# WhatFrankShould_veDone.net
KiCad netlist of a schematic drawn in EAGLE
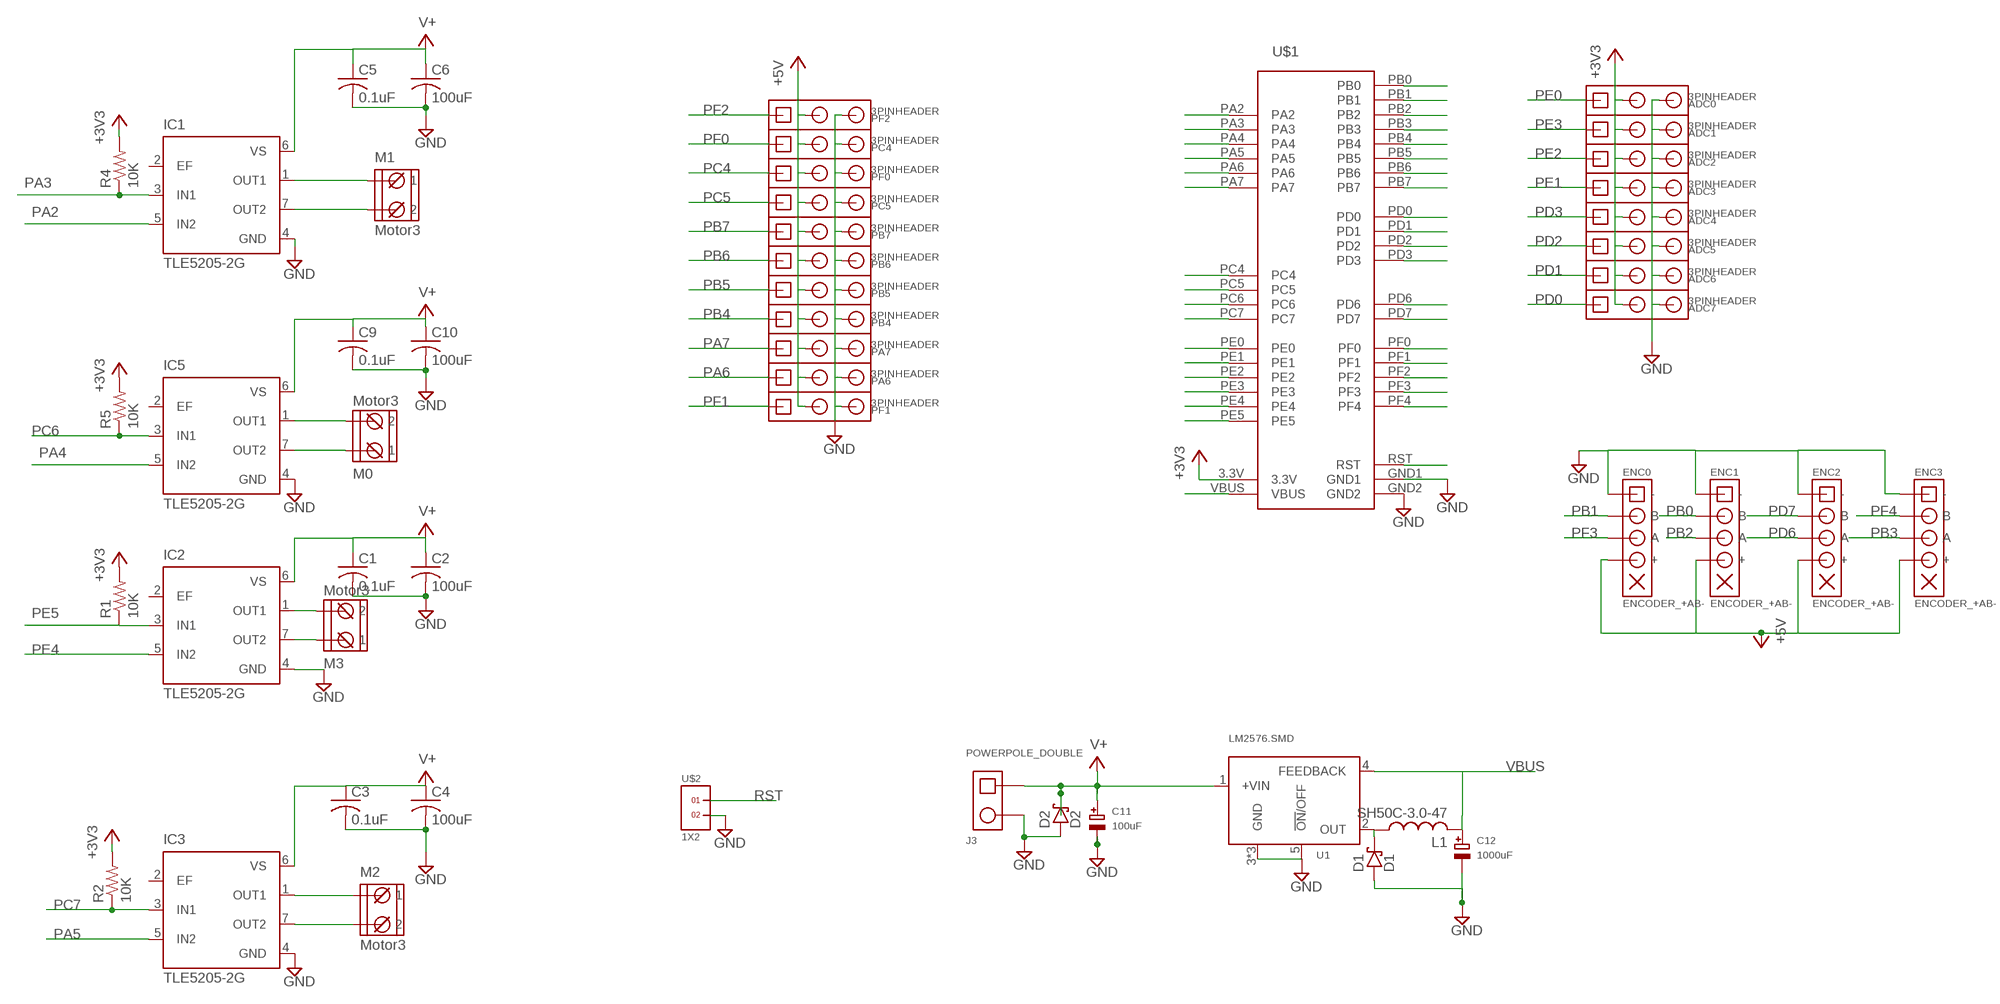
[diagram p0: schematic, sheet 1]

(export (version "E")
  (design (tool "Eeschema 10.0.6"))
  (components
    (comp (ref "ADC0")
      (value "3PINHEADER")
      (footprint "eagle-import:3PINHEADER")
      (libsource (lib "eagle-import") (part "3PINHEADER"))
    )
    (comp (ref "ADC1")
      (value "3PINHEADER")
      (footprint "eagle-import:3PINHEADER")
      (libsource (lib "eagle-import") (part "3PINHEADER"))
    )
    (comp (ref "ADC2")
      (value "3PINHEADER")
      (footprint "eagle-import:3PINHEADER")
      (libsource (lib "eagle-import") (part "3PINHEADER"))
    )
    (comp (ref "ADC3")
      (value "3PINHEADER")
      (footprint "eagle-import:3PINHEADER")
      (libsource (lib "eagle-import") (part "3PINHEADER"))
    )
    (comp (ref "ADC4")
      (value "3PINHEADER")
      (footprint "eagle-import:3PINHEADER")
      (libsource (lib "eagle-import") (part "3PINHEADER"))
    )
    (comp (ref "ADC5")
      (value "3PINHEADER")
      (footprint "eagle-import:3PINHEADER")
      (libsource (lib "eagle-import") (part "3PINHEADER"))
    )
    (comp (ref "ADC6")
      (value "3PINHEADER")
      (footprint "eagle-import:3PINHEADER")
      (libsource (lib "eagle-import") (part "3PINHEADER"))
    )
    (comp (ref "ADC7")
      (value "3PINHEADER")
      (footprint "eagle-import:3PINHEADER")
      (libsource (lib "eagle-import") (part "3PINHEADER"))
    )
    (comp (ref "C1")
      (value "0.1uF")
      (footprint "eagle-import:C0603")
      (libsource (lib "eagle-import") (part "C-USC0603"))
    )
    (comp (ref "C2")
      (value "100uF")
      (footprint "eagle-import:C0603")
      (libsource (lib "eagle-import") (part "C-USC0603"))
    )
    (comp (ref "C3")
      (value "0.1uF")
      (footprint "eagle-import:C0603")
      (libsource (lib "eagle-import") (part "C-USC0603"))
    )
    (comp (ref "C4")
      (value "100uF")
      (footprint "eagle-import:C0603")
      (libsource (lib "eagle-import") (part "C-USC0603"))
    )
    (comp (ref "C5")
      (value "0.1uF")
      (footprint "eagle-import:C0603")
      (libsource (lib "eagle-import") (part "C-USC0603"))
    )
    (comp (ref "C6")
      (value "100uF")
      (footprint "eagle-import:C0603")
      (libsource (lib "eagle-import") (part "C-USC0603"))
    )
    (comp (ref "C9")
      (value "0.1uF")
      (footprint "eagle-import:C0603")
      (libsource (lib "eagle-import") (part "C-USC0603"))
    )
    (comp (ref "C10")
      (value "100uF")
      (footprint "eagle-import:C0603")
      (libsource (lib "eagle-import") (part "C-USC0603"))
    )
    (comp (ref "C11")
      (value "100uF")
      (footprint "eagle-import:PANASONIC_D")
      (libsource (lib "eagle-import") (part "CAP_ELECTROLYTICPANASONIC_D"))
    )
    (comp (ref "C12")
      (value "1000uF")
      (footprint "eagle-import:PANASONIC_D")
      (libsource (lib "eagle-import") (part "CAP_ELECTROLYTICPANASONIC_D"))
    )
    (comp (ref "D1")
      (value "D1")
      (footprint "eagle-import:DIODE_17MM")
      (libsource (lib "eagle-import") (part "1N5820-D"))
    )
    (comp (ref "D2")
      (value "D2")
      (footprint "eagle-import:DIODE_17MM")
      (libsource (lib "eagle-import") (part "1N5820-D"))
    )
    (comp (ref "ENC0")
      (value "ENCODER_+AB-")
      (footprint "eagle-import:0.1IN_HEADER_1X5")
      (libsource (lib "eagle-import") (part "ENCODER_+AB-"))
    )
    (comp (ref "ENC1")
      (value "ENCODER_+AB-")
      (footprint "eagle-import:0.1IN_HEADER_1X5")
      (libsource (lib "eagle-import") (part "ENCODER_+AB-"))
    )
    (comp (ref "ENC2")
      (value "ENCODER_+AB-")
      (footprint "eagle-import:0.1IN_HEADER_1X5")
      (libsource (lib "eagle-import") (part "ENCODER_+AB-"))
    )
    (comp (ref "ENC3")
      (value "ENCODER_+AB-")
      (footprint "eagle-import:0.1IN_HEADER_1X5")
      (libsource (lib "eagle-import") (part "ENCODER_+AB-"))
    )
    (comp (ref "IC1")
      (value "TLE5205-2G")
      (footprint "eagle-import:P-TO263-7-1")
      (libsource (lib "eagle-import") (part "TLE5205-2G"))
    )
    (comp (ref "IC2")
      (value "TLE5205-2G")
      (footprint "eagle-import:P-TO263-7-1")
      (libsource (lib "eagle-import") (part "TLE5205-2G"))
    )
    (comp (ref "IC3")
      (value "TLE5205-2G")
      (footprint "eagle-import:P-TO263-7-1")
      (libsource (lib "eagle-import") (part "TLE5205-2G"))
    )
    (comp (ref "IC5")
      (value "TLE5205-2G")
      (footprint "eagle-import:P-TO263-7-1")
      (libsource (lib "eagle-import") (part "TLE5205-2G"))
    )
    (comp (ref "J3")
      (value "POWERPOLE_DOUBLE")
      (footprint "eagle-import:POWERPOLE_DOUBLE")
      (libsource (lib "eagle-import") (part "POWERPOLE_DOUBLE"))
    )
    (comp (ref "L1")
      (value "SH50C-3.0-47")
      (footprint "eagle-import:SH50-C2")
      (libsource (lib "eagle-import") (part "SH50C-3.0-47"))
    )
    (comp (ref "M0")
      (value "Motor3")
      (footprint "eagle-import:PHOENIXSCREWTERMINAL_2")
      (libsource (lib "eagle-import") (part "PHOENIXSCREWTERMINAL_2"))
    )
    (comp (ref "M1")
      (value "Motor3")
      (footprint "eagle-import:PHOENIXSCREWTERMINAL_2")
      (libsource (lib "eagle-import") (part "PHOENIXSCREWTERMINAL_2"))
    )
    (comp (ref "M2")
      (value "Motor3")
      (footprint "eagle-import:PHOENIXSCREWTERMINAL_2")
      (libsource (lib "eagle-import") (part "PHOENIXSCREWTERMINAL_2"))
    )
    (comp (ref "M3")
      (value "Motor3")
      (footprint "eagle-import:PHOENIXSCREWTERMINAL_2")
      (libsource (lib "eagle-import") (part "PHOENIXSCREWTERMINAL_2"))
    )
    (comp (ref "PA6")
      (value "3PINHEADER")
      (footprint "eagle-import:3PINHEADER")
      (libsource (lib "eagle-import") (part "3PINHEADER"))
    )
    (comp (ref "PA7")
      (value "3PINHEADER")
      (footprint "eagle-import:3PINHEADER")
      (libsource (lib "eagle-import") (part "3PINHEADER"))
    )
    (comp (ref "PB4")
      (value "3PINHEADER")
      (footprint "eagle-import:3PINHEADER")
      (libsource (lib "eagle-import") (part "3PINHEADER"))
    )
    (comp (ref "PB5")
      (value "3PINHEADER")
      (footprint "eagle-import:3PINHEADER")
      (libsource (lib "eagle-import") (part "3PINHEADER"))
    )
    (comp (ref "PB6")
      (value "3PINHEADER")
      (footprint "eagle-import:3PINHEADER")
      (libsource (lib "eagle-import") (part "3PINHEADER"))
    )
    (comp (ref "PB7")
      (value "3PINHEADER")
      (footprint "eagle-import:3PINHEADER")
      (libsource (lib "eagle-import") (part "3PINHEADER"))
    )
    (comp (ref "PC4")
      (value "3PINHEADER")
      (footprint "eagle-import:3PINHEADER")
      (libsource (lib "eagle-import") (part "3PINHEADER"))
    )
    (comp (ref "PC5")
      (value "3PINHEADER")
      (footprint "eagle-import:3PINHEADER")
      (libsource (lib "eagle-import") (part "3PINHEADER"))
    )
    (comp (ref "PF0")
      (value "3PINHEADER")
      (footprint "eagle-import:3PINHEADER")
      (libsource (lib "eagle-import") (part "3PINHEADER"))
    )
    (comp (ref "PF1")
      (value "3PINHEADER")
      (footprint "eagle-import:3PINHEADER")
      (libsource (lib "eagle-import") (part "3PINHEADER"))
    )
    (comp (ref "PF2")
      (value "3PINHEADER")
      (footprint "eagle-import:3PINHEADER")
      (libsource (lib "eagle-import") (part "3PINHEADER"))
    )
    (comp (ref "R1")
      (value "10K")
      (footprint "eagle-import:R0603")
      (libsource (lib "eagle-import") (part "R-US_R0603"))
    )
    (comp (ref "R2")
      (value "10K")
      (footprint "eagle-import:R0603")
      (libsource (lib "eagle-import") (part "R-US_R0603"))
    )
    (comp (ref "R4")
      (value "10K")
      (footprint "eagle-import:R0603")
      (libsource (lib "eagle-import") (part "R-US_R0603"))
    )
    (comp (ref "R5")
      (value "10K")
      (footprint "eagle-import:R0603")
      (libsource (lib "eagle-import") (part "R-US_R0603"))
    )
    (comp (ref "U$1")
      (value "STELLARIS-LAUNCHPADSTELLARIS-LAUNCHPAD-XL")
      (footprint "eagle-import:LAUNCHPAD-XL")
      (libsource (lib "eagle-import") (part "STELLARIS-LAUNCHPADSTELLARIS-LAUNCHPAD-XL"))
    )
    (comp (ref "U$2")
      (value "1X2")
      (footprint "eagle-import:1X2")
      (libsource (lib "eagle-import") (part "1X2"))
    )
    (comp (ref "U1")
      (value "LM2576.SMD")
      (footprint "eagle-import:KTT0005B")
      (libsource (lib "eagle-import") (part "LM2576.SMD"))
    )
  )
  (nets
    (net (code "1") (name "+3V3") (class "Default")
      (node (ref "ADC0") (pin "2") (pinfunction "2_2") (pintype "bidirectional"))
      (node (ref "ADC1") (pin "2") (pinfunction "2_2") (pintype "bidirectional"))
      (node (ref "ADC2") (pin "2") (pinfunction "2_2") (pintype "bidirectional"))
      (node (ref "ADC3") (pin "2") (pinfunction "2_2") (pintype "bidirectional"))
      (node (ref "ADC4") (pin "2") (pinfunction "2_2") (pintype "bidirectional"))
      (node (ref "ADC5") (pin "2") (pinfunction "2_2") (pintype "bidirectional"))
      (node (ref "ADC6") (pin "2") (pinfunction "2_2") (pintype "bidirectional"))
      (node (ref "ADC7") (pin "2") (pinfunction "2_2") (pintype "bidirectional"))
      (node (ref "R1") (pin "2") (pinfunction "2_2") (pintype "passive"))
      (node (ref "R2") (pin "2") (pinfunction "2_2") (pintype "passive"))
      (node (ref "R4") (pin "2") (pinfunction "2_2") (pintype "passive"))
      (node (ref "R5") (pin "2") (pinfunction "2_2") (pintype "passive"))
      (node (ref "U$1") (pin "3.3V") (pinfunction "3.3V_3.3V") (pintype "power_in"))
    )
    (net (code "2") (name "+5V") (class "Default")
      (node (ref "ENC0") (pin "4") (pinfunction "+_4") (pintype "bidirectional"))
      (node (ref "ENC1") (pin "4") (pinfunction "+_4") (pintype "bidirectional"))
      (node (ref "ENC2") (pin "4") (pinfunction "+_4") (pintype "bidirectional"))
      (node (ref "ENC3") (pin "4") (pinfunction "+_4") (pintype "bidirectional"))
      (node (ref "PA6") (pin "2") (pinfunction "2_2") (pintype "bidirectional"))
      (node (ref "PA7") (pin "2") (pinfunction "2_2") (pintype "bidirectional"))
      (node (ref "PB4") (pin "2") (pinfunction "2_2") (pintype "bidirectional"))
      (node (ref "PB5") (pin "2") (pinfunction "2_2") (pintype "bidirectional"))
      (node (ref "PB6") (pin "2") (pinfunction "2_2") (pintype "bidirectional"))
      (node (ref "PB7") (pin "2") (pinfunction "2_2") (pintype "bidirectional"))
      (node (ref "PC4") (pin "2") (pinfunction "2_2") (pintype "bidirectional"))
      (node (ref "PC5") (pin "2") (pinfunction "2_2") (pintype "bidirectional"))
      (node (ref "PF0") (pin "2") (pinfunction "2_2") (pintype "bidirectional"))
      (node (ref "PF1") (pin "2") (pinfunction "2_2") (pintype "bidirectional"))
      (node (ref "PF2") (pin "2") (pinfunction "2_2") (pintype "bidirectional"))
    )
    (net (code "3") (name "/PA2") (class "Default")
      (node (ref "IC1") (pin "5") (pinfunction "IN2_5") (pintype "input"))
      (node (ref "U$1") (pin "PA2") (pinfunction "PA2_PA2") (pintype "bidirectional"))
    )
    (net (code "4") (name "/PA3") (class "Default")
      (node (ref "IC1") (pin "3") (pinfunction "IN1_3") (pintype "input"))
      (node (ref "R4") (pin "1") (pinfunction "1_1") (pintype "passive"))
      (node (ref "U$1") (pin "PA3") (pinfunction "PA3_PA3") (pintype "bidirectional"))
    )
    (net (code "5") (name "/PA4") (class "Default")
      (node (ref "IC5") (pin "5") (pinfunction "IN2_5") (pintype "input"))
      (node (ref "U$1") (pin "PA4") (pinfunction "PA4_PA4") (pintype "bidirectional"))
    )
    (net (code "6") (name "/PA5") (class "Default")
      (node (ref "IC3") (pin "5") (pinfunction "IN2_5") (pintype "input"))
      (node (ref "U$1") (pin "PA5") (pinfunction "PA5_PA5") (pintype "bidirectional"))
    )
    (net (code "7") (name "/PA6") (class "Default")
      (node (ref "PA6") (pin "1") (pinfunction "1_1") (pintype "bidirectional"))
      (node (ref "U$1") (pin "PA6") (pinfunction "PA6_PA6") (pintype "bidirectional"))
    )
    (net (code "8") (name "/PA7") (class "Default")
      (node (ref "PA7") (pin "1") (pinfunction "1_1") (pintype "bidirectional"))
      (node (ref "U$1") (pin "PA7") (pinfunction "PA7_PA7") (pintype "bidirectional"))
    )
    (net (code "9") (name "/PB0") (class "Default")
      (node (ref "ENC1") (pin "2") (pinfunction "B_2") (pintype "bidirectional"))
      (node (ref "U$1") (pin "PB0") (pinfunction "PB0_PB0") (pintype "bidirectional"))
    )
    (net (code "10") (name "/PB1") (class "Default")
      (node (ref "ENC0") (pin "2") (pinfunction "B_2") (pintype "bidirectional"))
      (node (ref "U$1") (pin "PB1") (pinfunction "PB1_PB1") (pintype "bidirectional"))
    )
    (net (code "11") (name "/PB2") (class "Default")
      (node (ref "ENC1") (pin "3") (pinfunction "A_3") (pintype "bidirectional"))
      (node (ref "U$1") (pin "PB2") (pinfunction "PB2_PB2") (pintype "bidirectional"))
    )
    (net (code "12") (name "/PB3") (class "Default")
      (node (ref "ENC3") (pin "3") (pinfunction "A_3") (pintype "bidirectional"))
      (node (ref "U$1") (pin "PB3") (pinfunction "PB3_PB3") (pintype "bidirectional"))
    )
    (net (code "13") (name "/PB4") (class "Default")
      (node (ref "PB4") (pin "1") (pinfunction "1_1") (pintype "bidirectional"))
      (node (ref "U$1") (pin "PB4") (pinfunction "PB4_PB4") (pintype "bidirectional"))
    )
    (net (code "14") (name "/PB5") (class "Default")
      (node (ref "PB5") (pin "1") (pinfunction "1_1") (pintype "bidirectional"))
      (node (ref "U$1") (pin "PB5") (pinfunction "PB5_PB5") (pintype "bidirectional"))
    )
    (net (code "15") (name "/PB6") (class "Default")
      (node (ref "PB6") (pin "1") (pinfunction "1_1") (pintype "bidirectional"))
      (node (ref "U$1") (pin "PB6") (pinfunction "PB6_PB6") (pintype "bidirectional"))
    )
    (net (code "16") (name "/PB7") (class "Default")
      (node (ref "PB7") (pin "1") (pinfunction "1_1") (pintype "bidirectional"))
      (node (ref "U$1") (pin "PB7") (pinfunction "PB7_PB7") (pintype "bidirectional"))
    )
    (net (code "17") (name "/PC4") (class "Default")
      (node (ref "PF0") (pin "1") (pinfunction "1_1") (pintype "bidirectional"))
      (node (ref "U$1") (pin "PC4") (pinfunction "PC4_PC4") (pintype "bidirectional"))
    )
    (net (code "18") (name "/PC5") (class "Default")
      (node (ref "PC5") (pin "1") (pinfunction "1_1") (pintype "bidirectional"))
      (node (ref "U$1") (pin "PC5") (pinfunction "PC5_PC5") (pintype "bidirectional"))
    )
    (net (code "19") (name "/PC6") (class "Default")
      (node (ref "IC5") (pin "3") (pinfunction "IN1_3") (pintype "input"))
      (node (ref "R5") (pin "1") (pinfunction "1_1") (pintype "passive"))
      (node (ref "U$1") (pin "PC6") (pinfunction "PC6_PC6") (pintype "bidirectional"))
    )
    (net (code "20") (name "/PC7") (class "Default")
      (node (ref "IC3") (pin "3") (pinfunction "IN1_3") (pintype "input"))
      (node (ref "R2") (pin "1") (pinfunction "1_1") (pintype "passive"))
      (node (ref "U$1") (pin "PC7") (pinfunction "PC7_PC7") (pintype "bidirectional"))
    )
    (net (code "21") (name "/PD0") (class "Default")
      (node (ref "ADC7") (pin "1") (pinfunction "1_1") (pintype "bidirectional"))
      (node (ref "U$1") (pin "PD0") (pinfunction "PD0_PD0") (pintype "bidirectional"))
    )
    (net (code "22") (name "/PD1") (class "Default")
      (node (ref "ADC6") (pin "1") (pinfunction "1_1") (pintype "bidirectional"))
      (node (ref "U$1") (pin "PD1") (pinfunction "PD1_PD1") (pintype "bidirectional"))
    )
    (net (code "23") (name "/PD2") (class "Default")
      (node (ref "ADC5") (pin "1") (pinfunction "1_1") (pintype "bidirectional"))
      (node (ref "U$1") (pin "PD2") (pinfunction "PD2_PD2") (pintype "bidirectional"))
    )
    (net (code "24") (name "/PD3") (class "Default")
      (node (ref "ADC4") (pin "1") (pinfunction "1_1") (pintype "bidirectional"))
      (node (ref "U$1") (pin "PD3") (pinfunction "PD3_PD3") (pintype "bidirectional"))
    )
    (net (code "25") (name "/PD6") (class "Default")
      (node (ref "ENC2") (pin "3") (pinfunction "A_3") (pintype "bidirectional"))
      (node (ref "U$1") (pin "PD6") (pinfunction "PD6_PD6") (pintype "bidirectional"))
    )
    (net (code "26") (name "/PD7") (class "Default")
      (node (ref "ENC2") (pin "2") (pinfunction "B_2") (pintype "bidirectional"))
      (node (ref "U$1") (pin "PD7") (pinfunction "PD7_PD7") (pintype "bidirectional"))
    )
    (net (code "27") (name "/PE0") (class "Default")
      (node (ref "ADC0") (pin "1") (pinfunction "1_1") (pintype "bidirectional"))
      (node (ref "U$1") (pin "PE0") (pinfunction "PE0_PE0") (pintype "bidirectional"))
    )
    (net (code "28") (name "/PE1") (class "Default")
      (node (ref "ADC3") (pin "1") (pinfunction "1_1") (pintype "bidirectional"))
      (node (ref "U$1") (pin "PE1") (pinfunction "PE1_PE1") (pintype "bidirectional"))
    )
    (net (code "29") (name "/PE2") (class "Default")
      (node (ref "ADC2") (pin "1") (pinfunction "1_1") (pintype "bidirectional"))
      (node (ref "U$1") (pin "PE2") (pinfunction "PE2_PE2") (pintype "bidirectional"))
    )
    (net (code "30") (name "/PE3") (class "Default")
      (node (ref "ADC1") (pin "1") (pinfunction "1_1") (pintype "bidirectional"))
      (node (ref "U$1") (pin "PE3") (pinfunction "PE3_PE3") (pintype "bidirectional"))
    )
    (net (code "31") (name "/PE4") (class "Default")
      (node (ref "IC2") (pin "5") (pinfunction "IN2_5") (pintype "input"))
      (node (ref "U$1") (pin "PE4") (pinfunction "PE4_PE4") (pintype "bidirectional"))
    )
    (net (code "32") (name "/PE5") (class "Default")
      (node (ref "IC2") (pin "3") (pinfunction "IN1_3") (pintype "input"))
      (node (ref "R1") (pin "1") (pinfunction "1_1") (pintype "passive"))
      (node (ref "U$1") (pin "PE5") (pinfunction "PE5_PE5") (pintype "bidirectional"))
    )
    (net (code "33") (name "/PF0") (class "Default")
      (node (ref "PC4") (pin "1") (pinfunction "1_1") (pintype "bidirectional"))
      (node (ref "U$1") (pin "PF0") (pinfunction "PF0_PF0") (pintype "bidirectional"))
    )
    (net (code "34") (name "/PF1") (class "Default")
      (node (ref "PF1") (pin "1") (pinfunction "1_1") (pintype "bidirectional"))
      (node (ref "U$1") (pin "PF1") (pinfunction "PF1_PF1") (pintype "bidirectional"))
    )
    (net (code "35") (name "/PF2") (class "Default")
      (node (ref "PF2") (pin "1") (pinfunction "1_1") (pintype "bidirectional"))
      (node (ref "U$1") (pin "PF2") (pinfunction "PF2_PF2") (pintype "bidirectional"))
    )
    (net (code "36") (name "/PF3") (class "Default")
      (node (ref "ENC0") (pin "3") (pinfunction "A_3") (pintype "bidirectional"))
      (node (ref "U$1") (pin "PF3") (pinfunction "PF3_PF3") (pintype "bidirectional"))
    )
    (net (code "37") (name "/PF4") (class "Default")
      (node (ref "ENC3") (pin "2") (pinfunction "B_2") (pintype "bidirectional"))
      (node (ref "U$1") (pin "PF4") (pinfunction "PF4_PF4") (pintype "bidirectional"))
    )
    (net (code "38") (name "/RST") (class "Default")
      (node (ref "U$1") (pin "RST") (pinfunction "RST_RST") (pintype "power_in"))
      (node (ref "U$2") (pin "1") (pinfunction "1_1") (pintype "bidirectional"))
    )
    (net (code "39") (name "/VBUS") (class "Default")
      (node (ref "C12") (pin "+") (pinfunction "+_+") (pintype "passive"))
      (node (ref "L1") (pin "P$2") (pinfunction "2_P$2") (pintype "passive"))
      (node (ref "U$1") (pin "VBUS") (pinfunction "VBUS_VBUS") (pintype "power_in"))
      (node (ref "U1") (pin "4") (pinfunction "FEEDBACK_4") (pintype "bidirectional"))
    )
    (net (code "40") (name "GND") (class "Default")
      (node (ref "ADC0") (pin "3") (pinfunction "3_3") (pintype "bidirectional"))
      (node (ref "ADC1") (pin "3") (pinfunction "3_3") (pintype "bidirectional"))
      (node (ref "ADC2") (pin "3") (pinfunction "3_3") (pintype "bidirectional"))
      (node (ref "ADC3") (pin "3") (pinfunction "3_3") (pintype "bidirectional"))
      (node (ref "ADC4") (pin "3") (pinfunction "3_3") (pintype "bidirectional"))
      (node (ref "ADC5") (pin "3") (pinfunction "3_3") (pintype "bidirectional"))
      (node (ref "ADC6") (pin "3") (pinfunction "3_3") (pintype "bidirectional"))
      (node (ref "ADC7") (pin "3") (pinfunction "3_3") (pintype "bidirectional"))
      (node (ref "C1") (pin "2") (pinfunction "2_2") (pintype "passive"))
      (node (ref "C10") (pin "2") (pinfunction "2_2") (pintype "passive"))
      (node (ref "C11") (pin "-") (pinfunction "-_-") (pintype "passive"))
      (node (ref "C12") (pin "-") (pinfunction "-_-") (pintype "passive"))
      (node (ref "C2") (pin "2") (pinfunction "2_2") (pintype "passive"))
      (node (ref "C3") (pin "2") (pinfunction "2_2") (pintype "passive"))
      (node (ref "C4") (pin "2") (pinfunction "2_2") (pintype "passive"))
      (node (ref "C5") (pin "2") (pinfunction "2_2") (pintype "passive"))
      (node (ref "C6") (pin "2") (pinfunction "2_2") (pintype "passive"))
      (node (ref "C9") (pin "2") (pinfunction "2_2") (pintype "passive"))
      (node (ref "D1") (pin "2") (pinfunction "A_2") (pintype "passive"))
      (node (ref "D2") (pin "2") (pinfunction "A_2") (pintype "passive"))
      (node (ref "ENC0") (pin "1") (pinfunction "-_1") (pintype "bidirectional"))
      (node (ref "ENC1") (pin "1") (pinfunction "-_1") (pintype "bidirectional"))
      (node (ref "ENC2") (pin "1") (pinfunction "-_1") (pintype "bidirectional"))
      (node (ref "ENC3") (pin "1") (pinfunction "-_1") (pintype "bidirectional"))
      (node (ref "IC1") (pin "4") (pinfunction "GND_4") (pintype "power_in"))
      (node (ref "IC2") (pin "4") (pinfunction "GND_4") (pintype "power_in"))
      (node (ref "IC3") (pin "4") (pinfunction "GND_4") (pintype "power_in"))
      (node (ref "IC5") (pin "4") (pinfunction "GND_4") (pintype "power_in"))
      (node (ref "J3") (pin "2") (pinfunction "2_2") (pintype "bidirectional"))
      (node (ref "PA6") (pin "3") (pinfunction "3_3") (pintype "bidirectional"))
      (node (ref "PA7") (pin "3") (pinfunction "3_3") (pintype "bidirectional"))
      (node (ref "PB4") (pin "3") (pinfunction "3_3") (pintype "bidirectional"))
      (node (ref "PB5") (pin "3") (pinfunction "3_3") (pintype "bidirectional"))
      (node (ref "PB6") (pin "3") (pinfunction "3_3") (pintype "bidirectional"))
      (node (ref "PB7") (pin "3") (pinfunction "3_3") (pintype "bidirectional"))
      (node (ref "PC4") (pin "3") (pinfunction "3_3") (pintype "bidirectional"))
      (node (ref "PC5") (pin "3") (pinfunction "3_3") (pintype "bidirectional"))
      (node (ref "PF0") (pin "3") (pinfunction "3_3") (pintype "bidirectional"))
      (node (ref "PF1") (pin "3") (pinfunction "3_3") (pintype "bidirectional"))
      (node (ref "PF2") (pin "3") (pinfunction "3_3") (pintype "bidirectional"))
      (node (ref "U$1") (pin "GND1") (pinfunction "GND1_GND1") (pintype "bidirectional"))
      (node (ref "U$1") (pin "GND2") (pinfunction "GND2_GND2") (pintype "power_in"))
      (node (ref "U$2") (pin "2") (pinfunction "2_2") (pintype "bidirectional"))
      (node (ref "U1") (pin "3") (pinfunction "GND_3") (pintype "bidirectional"))
      (node (ref "U1") (pin "5") (pinfunction "~{ON}/OFF_5") (pintype "bidirectional"))
      (node (ref "U1") (pin "GROUND") (pinfunction "GND_GROUND") (pintype "bidirectional"))
      (node (ref "U1") (pin "GROUND@1") (pinfunction "GND_GROUND@1") (pintype "bidirectional"))
    )
    (net (code "41") (name "Net-(D1-C)") (class "Default")
      (node (ref "D1") (pin "1") (pinfunction "C_1") (pintype "passive"))
      (node (ref "L1") (pin "P$1") (pinfunction "1_P$1") (pintype "passive"))
      (node (ref "U1") (pin "2") (pinfunction "OUT_2") (pintype "bidirectional"))
    )
    (net (code "42") (name "Net-(IC1-OUT1)") (class "Default")
      (node (ref "IC1") (pin "1") (pinfunction "OUT1_1") (pintype "output"))
      (node (ref "M1") (pin "1") (pinfunction "1_1") (pintype "bidirectional"))
    )
    (net (code "43") (name "Net-(IC1-OUT2)") (class "Default")
      (node (ref "IC1") (pin "7") (pinfunction "OUT2_7") (pintype "output"))
      (node (ref "M1") (pin "2") (pinfunction "2_2") (pintype "bidirectional"))
    )
    (net (code "44") (name "Net-(IC2-OUT1)") (class "Default")
      (node (ref "IC2") (pin "1") (pinfunction "OUT1_1") (pintype "output"))
      (node (ref "M3") (pin "2") (pinfunction "2_2") (pintype "bidirectional"))
    )
    (net (code "45") (name "Net-(IC2-OUT2)") (class "Default")
      (node (ref "IC2") (pin "7") (pinfunction "OUT2_7") (pintype "output"))
      (node (ref "M3") (pin "1") (pinfunction "1_1") (pintype "bidirectional"))
    )
    (net (code "46") (name "Net-(IC3-OUT1)") (class "Default")
      (node (ref "IC3") (pin "1") (pinfunction "OUT1_1") (pintype "output"))
      (node (ref "M2") (pin "1") (pinfunction "1_1") (pintype "bidirectional"))
    )
    (net (code "47") (name "Net-(IC3-OUT2)") (class "Default")
      (node (ref "IC3") (pin "7") (pinfunction "OUT2_7") (pintype "output"))
      (node (ref "M2") (pin "2") (pinfunction "2_2") (pintype "bidirectional"))
    )
    (net (code "48") (name "Net-(IC5-OUT1)") (class "Default")
      (node (ref "IC5") (pin "1") (pinfunction "OUT1_1") (pintype "output"))
      (node (ref "M0") (pin "2") (pinfunction "2_2") (pintype "bidirectional"))
    )
    (net (code "49") (name "Net-(IC5-OUT2)") (class "Default")
      (node (ref "IC5") (pin "7") (pinfunction "OUT2_7") (pintype "output"))
      (node (ref "M0") (pin "1") (pinfunction "1_1") (pintype "bidirectional"))
    )
    (net (code "50") (name "V+") (class "Default")
      (node (ref "C1") (pin "1") (pinfunction "1_1") (pintype "passive"))
      (node (ref "C10") (pin "1") (pinfunction "1_1") (pintype "passive"))
      (node (ref "C11") (pin "+") (pinfunction "+_+") (pintype "passive"))
      (node (ref "C2") (pin "1") (pinfunction "1_1") (pintype "passive"))
      (node (ref "C3") (pin "1") (pinfunction "1_1") (pintype "passive"))
      (node (ref "C4") (pin "1") (pinfunction "1_1") (pintype "passive"))
      (node (ref "C5") (pin "1") (pinfunction "1_1") (pintype "passive"))
      (node (ref "C6") (pin "1") (pinfunction "1_1") (pintype "passive"))
      (node (ref "C9") (pin "1") (pinfunction "1_1") (pintype "passive"))
      (node (ref "D2") (pin "1") (pinfunction "C_1") (pintype "passive"))
      (node (ref "IC1") (pin "6") (pinfunction "VS_6") (pintype "input"))
      (node (ref "IC2") (pin "6") (pinfunction "VS_6") (pintype "input"))
      (node (ref "IC3") (pin "6") (pinfunction "VS_6") (pintype "input"))
      (node (ref "IC5") (pin "6") (pinfunction "VS_6") (pintype "input"))
      (node (ref "J3") (pin "1") (pinfunction "1_1") (pintype "bidirectional"))
      (node (ref "U1") (pin "1") (pinfunction "+VIN_1") (pintype "bidirectional"))
    )
    (net (code "51") (name "unconnected-(ENC0-X-Pad5)") (class "Default")
      (node (ref "ENC0") (pin "5") (pinfunction "X_5") (pintype "bidirectional"))
    )
    (net (code "52") (name "unconnected-(ENC1-X-Pad5)") (class "Default")
      (node (ref "ENC1") (pin "5") (pinfunction "X_5") (pintype "bidirectional"))
    )
    (net (code "53") (name "unconnected-(ENC2-X-Pad5)") (class "Default")
      (node (ref "ENC2") (pin "5") (pinfunction "X_5") (pintype "bidirectional"))
    )
    (net (code "54") (name "unconnected-(ENC3-X-Pad5)") (class "Default")
      (node (ref "ENC3") (pin "5") (pinfunction "X_5") (pintype "bidirectional"))
    )
    (net (code "55") (name "unconnected-(IC1-EF-Pad2)") (class "Default")
      (node (ref "IC1") (pin "2") (pinfunction "EF_2") (pintype "open_collector"))
    )
    (net (code "56") (name "unconnected-(IC2-EF-Pad2)") (class "Default")
      (node (ref "IC2") (pin "2") (pinfunction "EF_2") (pintype "open_collector"))
    )
    (net (code "57") (name "unconnected-(IC3-EF-Pad2)") (class "Default")
      (node (ref "IC3") (pin "2") (pinfunction "EF_2") (pintype "open_collector"))
    )
    (net (code "58") (name "unconnected-(IC5-EF-Pad2)") (class "Default")
      (node (ref "IC5") (pin "2") (pinfunction "EF_2") (pintype "open_collector"))
    )
  )
)
